# IntUltiMem_proto2.net
KiCad netlist of a schematic drawn in EAGLE
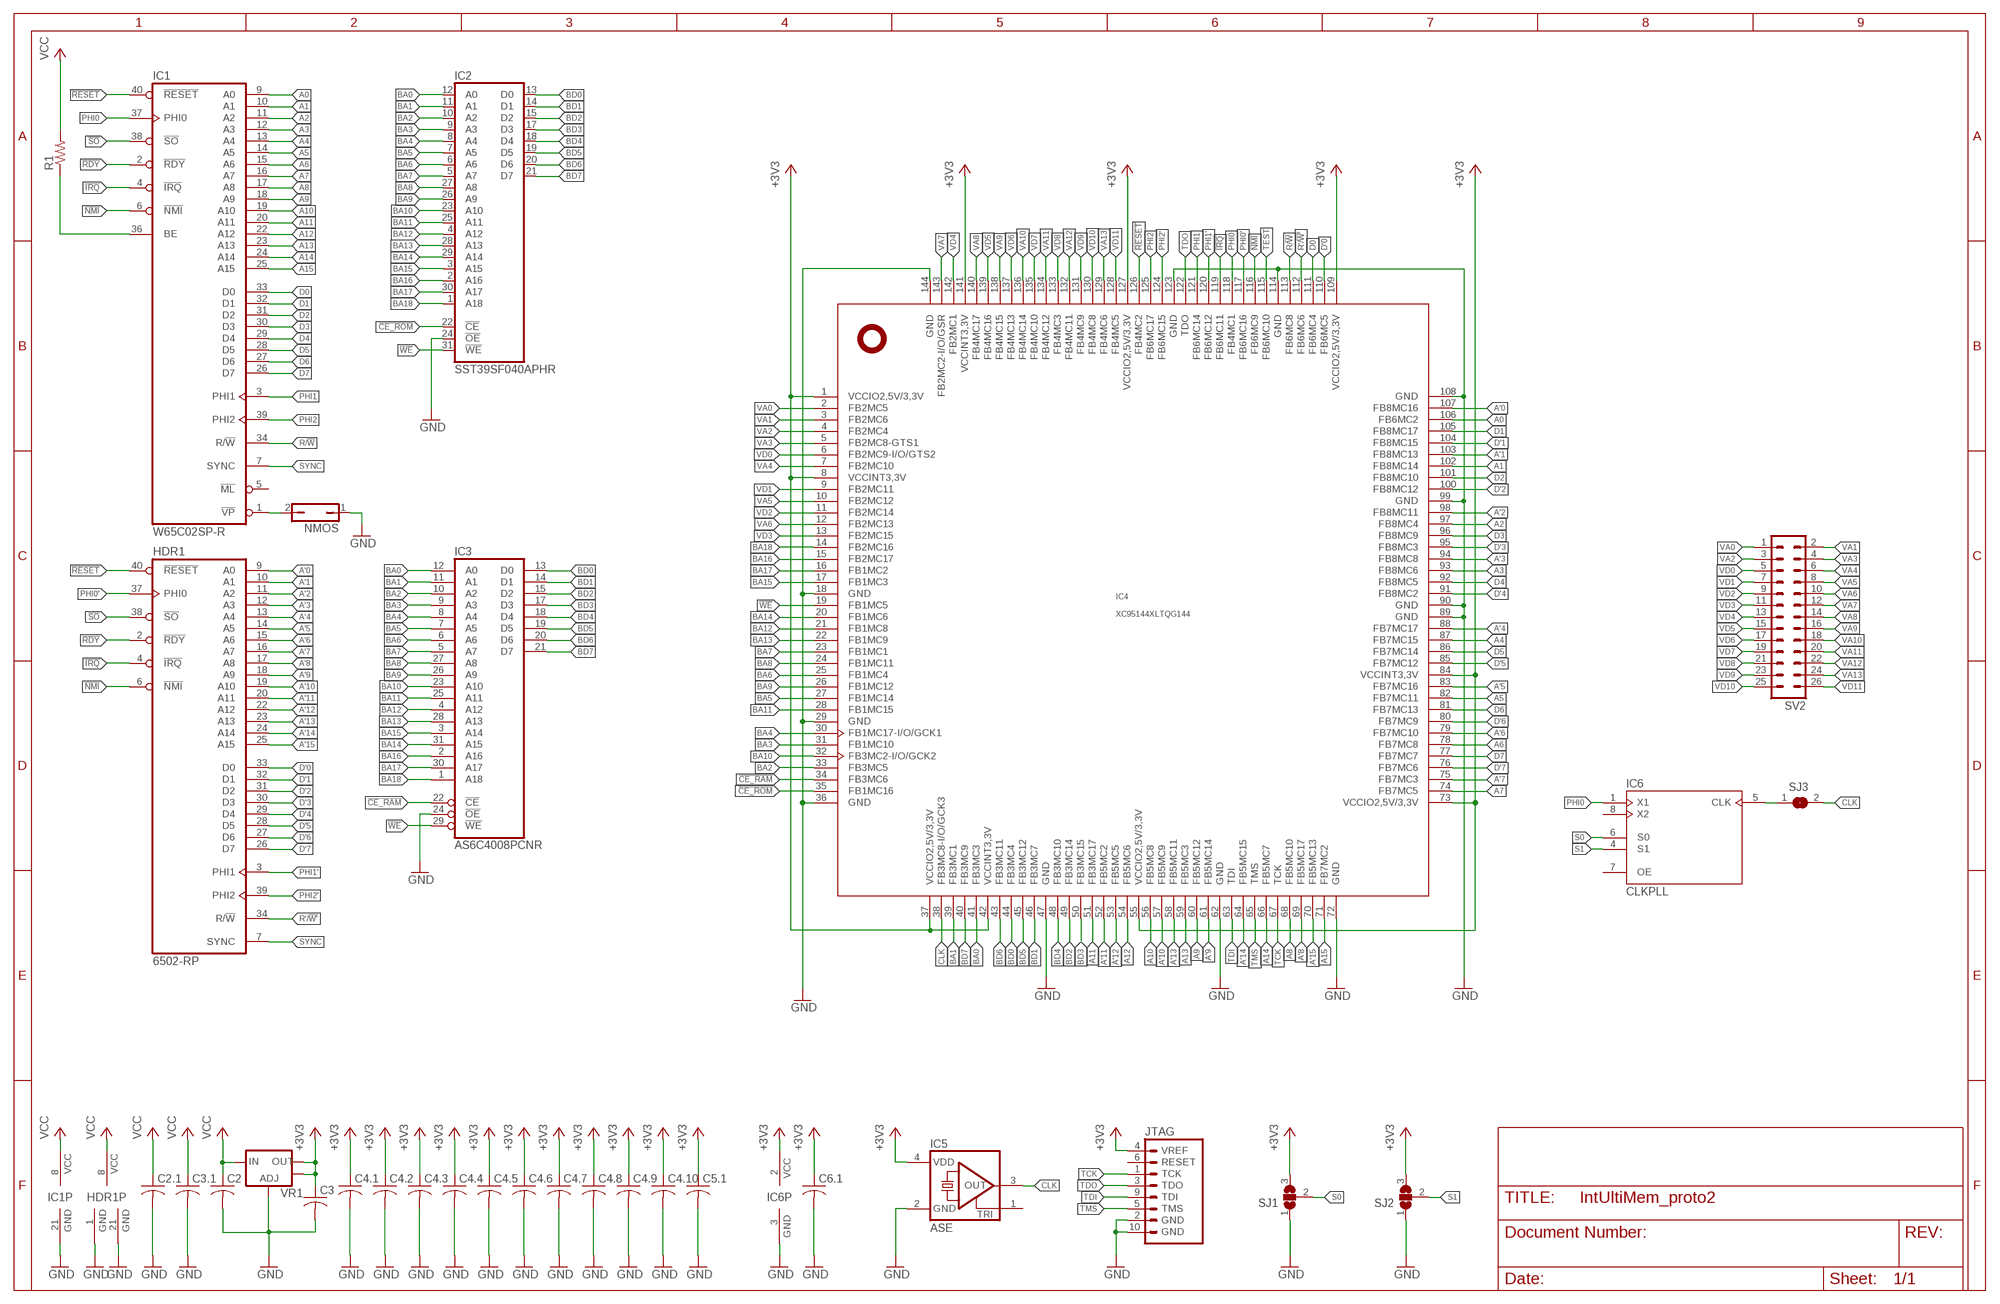
[diagram p0: schematic, sheet 1]

(export (version "E")
  (design (tool "Eeschema 10.0.6"))
  (components
    (comp (ref "C2")
      (value "C-USC0805")
      (footprint "eagle-import:C0805")
      (libsource (lib "eagle-import") (part "C-USC0805"))
    )
    (comp (ref "C2.1")
      (value "C-USC0402")
      (footprint "eagle-import:C0402")
      (libsource (lib "eagle-import") (part "C-USC0402"))
    )
    (comp (ref "C3")
      (value "C-USC0805")
      (footprint "eagle-import:C0805")
      (libsource (lib "eagle-import") (part "C-USC0805"))
    )
    (comp (ref "C3.1")
      (value "C-USC0402")
      (footprint "eagle-import:C0402")
      (libsource (lib "eagle-import") (part "C-USC0402"))
    )
    (comp (ref "C4.1")
      (value "C-USC0402")
      (footprint "eagle-import:C0402")
      (libsource (lib "eagle-import") (part "C-USC0402"))
    )
    (comp (ref "C4.2")
      (value "C-USC0402")
      (footprint "eagle-import:C0402")
      (libsource (lib "eagle-import") (part "C-USC0402"))
    )
    (comp (ref "C4.3")
      (value "C-USC0402")
      (footprint "eagle-import:C0402")
      (libsource (lib "eagle-import") (part "C-USC0402"))
    )
    (comp (ref "C4.4")
      (value "C-USC0402")
      (footprint "eagle-import:C0402")
      (libsource (lib "eagle-import") (part "C-USC0402"))
    )
    (comp (ref "C4.5")
      (value "C-USC0402")
      (footprint "eagle-import:C0402")
      (libsource (lib "eagle-import") (part "C-USC0402"))
    )
    (comp (ref "C4.6")
      (value "C-USC0402")
      (footprint "eagle-import:C0402")
      (libsource (lib "eagle-import") (part "C-USC0402"))
    )
    (comp (ref "C4.7")
      (value "C-USC0402")
      (footprint "eagle-import:C0402")
      (libsource (lib "eagle-import") (part "C-USC0402"))
    )
    (comp (ref "C4.8")
      (value "C-USC0402")
      (footprint "eagle-import:C0402")
      (libsource (lib "eagle-import") (part "C-USC0402"))
    )
    (comp (ref "C4.9")
      (value "C-USC0402")
      (footprint "eagle-import:C0402")
      (libsource (lib "eagle-import") (part "C-USC0402"))
    )
    (comp (ref "C4.10")
      (value "C-USC0402")
      (footprint "eagle-import:C0402")
      (libsource (lib "eagle-import") (part "C-USC0402"))
    )
    (comp (ref "C5.1")
      (value "C-USC0402")
      (footprint "eagle-import:C0402")
      (libsource (lib "eagle-import") (part "C-USC0402"))
    )
    (comp (ref "C6.1")
      (value "C-USC0402")
      (footprint "eagle-import:C0402")
      (libsource (lib "eagle-import") (part "C-USC0402"))
    )
    (comp (ref "HDR1")
      (value "6502-RP")
      (footprint "eagle-import:DIL40-ROUNDPAD")
      (libsource (lib "eagle-import") (part "6502-RP"))
    )
    (comp (ref "IC1")
      (value "W65C02SP-R")
      (footprint "eagle-import:DIL40-ROUNDPAD")
      (libsource (lib "eagle-import") (part "W65C02SP-R"))
    )
    (comp (ref "IC2")
      (value "SST39SF040APHR")
      (footprint "eagle-import:DIL32-RP")
      (libsource (lib "eagle-import") (part "SST39SF040APHR"))
    )
    (comp (ref "IC3")
      (value "AS6C4008PCNR")
      (footprint "eagle-import:DIL32-RP")
      (libsource (lib "eagle-import") (part "AS6C4008PCNR"))
    )
    (comp (ref "IC4")
      (value "XC95144XLTQG144")
      (footprint "eagle-import:TQFP144")
      (libsource (lib "eagle-import") (part "XC95144XLTQG144"))
    )
    (comp (ref "IC5")
      (value "ASE")
      (footprint "eagle-import:ASE")
      (libsource (lib "eagle-import") (part "ASE"))
    )
    (comp (ref "IC6")
      (value "CLKPLL")
      (footprint "eagle-import:SOIC8")
      (libsource (lib "eagle-import") (part "CLKPLL"))
    )
    (comp (ref "JTAG")
      (value "JTAG")
      (footprint "eagle-import:JTAG")
      (libsource (lib "eagle-import") (part "JTAG"))
    )
    (comp (ref "NMOS")
      (value "JP1Q")
      (footprint "eagle-import:JP1")
      (libsource (lib "eagle-import") (part "JP1Q"))
    )
    (comp (ref "R1")
      (value "R-US_R0402")
      (footprint "eagle-import:R0402")
      (libsource (lib "eagle-import") (part "R-US_R0402"))
    )
    (comp (ref "SJ1")
      (value "SJ2W")
      (footprint "eagle-import:SJ_2")
      (libsource (lib "eagle-import") (part "SJ2W"))
    )
    (comp (ref "SJ2")
      (value "SJ2W")
      (footprint "eagle-import:SJ_2")
      (libsource (lib "eagle-import") (part "SJ2W"))
    )
    (comp (ref "SJ3") (value "SJ") (footprint "eagle-import:SJ") (libsource (lib "eagle-import") (part "SJ")))
    (comp (ref "SV2")
      (value "MA13-2")
      (footprint "eagle-import:MA13-2")
      (libsource (lib "eagle-import") (part "MA13-2"))
    )
    (comp (ref "VR1")
      (value "V_REG_LM1117SOT223")
      (footprint "eagle-import:SOT223")
      (libsource (lib "eagle-import") (part "V_REG_LM1117SOT223"))
    )
  )
  (nets
    (net (code "1") (name "+3V3") (class "Default")
      (node (ref "C3") (pin "1") (pinfunction "1_1") (pintype "passive"))
      (node (ref "C4.1") (pin "1") (pinfunction "1_1") (pintype "passive"))
      (node (ref "C4.10") (pin "1") (pinfunction "1_1") (pintype "passive"))
      (node (ref "C4.2") (pin "1") (pinfunction "1_1") (pintype "passive"))
      (node (ref "C4.3") (pin "1") (pinfunction "1_1") (pintype "passive"))
      (node (ref "C4.4") (pin "1") (pinfunction "1_1") (pintype "passive"))
      (node (ref "C4.5") (pin "1") (pinfunction "1_1") (pintype "passive"))
      (node (ref "C4.6") (pin "1") (pinfunction "1_1") (pintype "passive"))
      (node (ref "C4.7") (pin "1") (pinfunction "1_1") (pintype "passive"))
      (node (ref "C4.8") (pin "1") (pinfunction "1_1") (pintype "passive"))
      (node (ref "C4.9") (pin "1") (pinfunction "1_1") (pintype "passive"))
      (node (ref "C5.1") (pin "1") (pinfunction "1_1") (pintype "passive"))
      (node (ref "C6.1") (pin "1") (pinfunction "1_1") (pintype "passive"))
      (node (ref "IC4") (pin "1") (pinfunction "VCCIO2,5V/3,3V_1") (pintype "power_in"))
      (node (ref "IC4") (pin "109") (pinfunction "VCCIO2,5V/3,3V_109") (pintype "power_in"))
      (node (ref "IC4") (pin "127") (pinfunction "VCCIO2,5V/3,3V_127") (pintype "power_in"))
      (node (ref "IC4") (pin "141") (pinfunction "VCCINT3,3V_141") (pintype "power_in"))
      (node (ref "IC4") (pin "37") (pinfunction "VCCIO2,5V/3,3V_37") (pintype "power_in"))
      (node (ref "IC4") (pin "42") (pinfunction "VCCINT3,3V_42") (pintype "power_in"))
      (node (ref "IC4") (pin "55") (pinfunction "VCCIO2,5V/3,3V_55") (pintype "power_in"))
      (node (ref "IC4") (pin "73") (pinfunction "VCCIO2,5V/3,3V_73") (pintype "power_in"))
      (node (ref "IC4") (pin "8") (pinfunction "VCCINT3,3V_8") (pintype "power_in"))
      (node (ref "IC4") (pin "84") (pinfunction "VCCINT3,3V_84") (pintype "power_in"))
      (node (ref "IC5") (pin "4") (pinfunction "VDD_4") (pintype "power_in"))
      (node (ref "IC6") (pin "2") (pinfunction "VCC_2") (pintype "power_in"))
      (node (ref "JTAG") (pin "4") (pinfunction "VREF_4") (pintype "power_in"))
      (node (ref "SJ1") (pin "3") (pinfunction "3_3") (pintype "passive"))
      (node (ref "SJ2") (pin "3") (pinfunction "3_3") (pintype "passive"))
      (node (ref "VR1") (pin "2") (pinfunction "OUT_2") (pintype "output"))
      (node (ref "VR1") (pin "4") (pinfunction "OUT_4") (pintype "output"))
    )
    (net (code "2") (name "/R'{slash}~{W'}") (class "Default")
      (node (ref "HDR1") (pin "34") (pinfunction "R/~{W}_34") (pintype "output"))
      (node (ref "IC4") (pin "112") (pinfunction "FB6MC6_112") (pintype "bidirectional"))
    )
    (net (code "3") (name "/R{slash}~{W}") (class "Default")
      (node (ref "IC1") (pin "34") (pinfunction "R/~{W}_34") (pintype "output"))
      (node (ref "IC4") (pin "113") (pinfunction "FB6MC8_113") (pintype "bidirectional"))
    )
    (net (code "4") (name "/~{CE_RAM}") (class "Default")
      (node (ref "IC3") (pin "22") (pinfunction "~{CE}_22") (pintype "input"))
      (node (ref "IC4") (pin "34") (pinfunction "FB3MC6_34") (pintype "bidirectional"))
    )
    (net (code "5") (name "/~{CE_ROM}") (class "Default")
      (node (ref "IC2") (pin "22") (pinfunction "~{CE}_22") (pintype "input"))
      (node (ref "IC4") (pin "35") (pinfunction "FB1MC16_35") (pintype "bidirectional"))
    )
    (net (code "6") (name "/~{IRQ}") (class "Default")
      (node (ref "HDR1") (pin "4") (pinfunction "~{IRQ}_4") (pintype "input"))
      (node (ref "IC1") (pin "4") (pinfunction "~{IRQ}_4") (pintype "input"))
      (node (ref "IC4") (pin "119") (pinfunction "FB6MC11_119") (pintype "bidirectional"))
    )
    (net (code "7") (name "/~{NMI}") (class "Default")
      (node (ref "HDR1") (pin "6") (pinfunction "~{NMI}_6") (pintype "input"))
      (node (ref "IC1") (pin "6") (pinfunction "~{NMI}_6") (pintype "input"))
      (node (ref "IC4") (pin "116") (pinfunction "FB6MC9_116") (pintype "bidirectional"))
    )
    (net (code "8") (name "/~{RDY}") (class "Default")
      (node (ref "HDR1") (pin "2") (pinfunction "~{RDY}_2") (pintype "input"))
      (node (ref "IC1") (pin "2") (pinfunction "~{RDY}_2") (pintype "bidirectional"))
    )
    (net (code "9") (name "/~{RESET}") (class "Default")
      (node (ref "HDR1") (pin "40") (pinfunction "~{RESET}_40") (pintype "input"))
      (node (ref "IC1") (pin "40") (pinfunction "~{RESET}_40") (pintype "input"))
      (node (ref "IC4") (pin "126") (pinfunction "FB4MC2_126") (pintype "bidirectional"))
    )
    (net (code "10") (name "/~{SO}") (class "Default")
      (node (ref "HDR1") (pin "38") (pinfunction "~{SO}_38") (pintype "input"))
      (node (ref "IC1") (pin "38") (pinfunction "~{SO}_38") (pintype "input"))
    )
    (net (code "11") (name "/~{WE}") (class "Default")
      (node (ref "IC2") (pin "31") (pinfunction "~{WE}_31") (pintype "input"))
      (node (ref "IC3") (pin "29") (pinfunction "~{WE}_29") (pintype "input"))
      (node (ref "IC4") (pin "19") (pinfunction "FB1MC5_19") (pintype "bidirectional"))
    )
    (net (code "12") (name "A'0") (class "Default")
      (node (ref "HDR1") (pin "9") (pinfunction "A0_9") (pintype "output"))
      (node (ref "IC4") (pin "107") (pinfunction "FB8MC16_107") (pintype "bidirectional"))
    )
    (net (code "13") (name "A'1") (class "Default")
      (node (ref "HDR1") (pin "10") (pinfunction "A1_10") (pintype "output"))
      (node (ref "IC4") (pin "103") (pinfunction "FB8MC13_103") (pintype "bidirectional"))
    )
    (net (code "14") (name "A'2") (class "Default")
      (node (ref "HDR1") (pin "11") (pinfunction "A2_11") (pintype "output"))
      (node (ref "IC4") (pin "98") (pinfunction "FB8MC11_98") (pintype "bidirectional"))
    )
    (net (code "15") (name "A'3") (class "Default")
      (node (ref "HDR1") (pin "12") (pinfunction "A3_12") (pintype "output"))
      (node (ref "IC4") (pin "94") (pinfunction "FB8MC8_94") (pintype "bidirectional"))
    )
    (net (code "16") (name "A'4") (class "Default")
      (node (ref "HDR1") (pin "13") (pinfunction "A4_13") (pintype "output"))
      (node (ref "IC4") (pin "88") (pinfunction "FB7MC17_88") (pintype "bidirectional"))
    )
    (net (code "17") (name "A'5") (class "Default")
      (node (ref "HDR1") (pin "14") (pinfunction "A5_14") (pintype "output"))
      (node (ref "IC4") (pin "83") (pinfunction "FB7MC16_83") (pintype "bidirectional"))
    )
    (net (code "18") (name "A'6") (class "Default")
      (node (ref "HDR1") (pin "15") (pinfunction "A6_15") (pintype "output"))
      (node (ref "IC4") (pin "79") (pinfunction "FB7MC10_79") (pintype "bidirectional"))
    )
    (net (code "19") (name "A'7") (class "Default")
      (node (ref "HDR1") (pin "16") (pinfunction "A7_16") (pintype "output"))
      (node (ref "IC4") (pin "75") (pinfunction "FB7MC3_75") (pintype "bidirectional"))
    )
    (net (code "20") (name "A'8") (class "Default")
      (node (ref "HDR1") (pin "17") (pinfunction "A8_17") (pintype "output"))
      (node (ref "IC4") (pin "69") (pinfunction "FB5MC17_69") (pintype "bidirectional"))
    )
    (net (code "21") (name "A'9") (class "Default")
      (node (ref "HDR1") (pin "18") (pinfunction "A9_18") (pintype "output"))
      (node (ref "IC4") (pin "61") (pinfunction "FB5MC14_61") (pintype "bidirectional"))
    )
    (net (code "22") (name "A'10") (class "Default")
      (node (ref "HDR1") (pin "19") (pinfunction "A10_19") (pintype "output"))
      (node (ref "IC4") (pin "57") (pinfunction "FB5MC9_57") (pintype "bidirectional"))
    )
    (net (code "23") (name "A'11") (class "Default")
      (node (ref "HDR1") (pin "20") (pinfunction "A11_20") (pintype "output"))
      (node (ref "IC4") (pin "52") (pinfunction "FB5MC2_52") (pintype "bidirectional"))
    )
    (net (code "24") (name "A'12") (class "Default")
      (node (ref "HDR1") (pin "22") (pinfunction "A12_22") (pintype "output"))
      (node (ref "IC4") (pin "53") (pinfunction "FB5MC5_53") (pintype "bidirectional"))
    )
    (net (code "25") (name "A'13") (class "Default")
      (node (ref "HDR1") (pin "23") (pinfunction "A13_23") (pintype "output"))
      (node (ref "IC4") (pin "58") (pinfunction "FB5MC11_58") (pintype "bidirectional"))
    )
    (net (code "26") (name "A'14") (class "Default")
      (node (ref "HDR1") (pin "24") (pinfunction "A14_24") (pintype "output"))
      (node (ref "IC4") (pin "64") (pinfunction "FB5MC15_64") (pintype "bidirectional"))
    )
    (net (code "27") (name "A'15") (class "Default")
      (node (ref "HDR1") (pin "25") (pinfunction "A15_25") (pintype "output"))
      (node (ref "IC4") (pin "70") (pinfunction "FB5MC13_70") (pintype "bidirectional"))
    )
    (net (code "28") (name "A0") (class "Default")
      (node (ref "IC1") (pin "9") (pinfunction "A0_9") (pintype "bidirectional"))
      (node (ref "IC4") (pin "106") (pinfunction "FB6MC2_106") (pintype "bidirectional"))
    )
    (net (code "29") (name "A1") (class "Default")
      (node (ref "IC1") (pin "10") (pinfunction "A1_10") (pintype "bidirectional"))
      (node (ref "IC4") (pin "102") (pinfunction "FB8MC14_102") (pintype "bidirectional"))
    )
    (net (code "30") (name "A2") (class "Default")
      (node (ref "IC1") (pin "11") (pinfunction "A2_11") (pintype "bidirectional"))
      (node (ref "IC4") (pin "97") (pinfunction "FB8MC4_97") (pintype "bidirectional"))
    )
    (net (code "31") (name "A3") (class "Default")
      (node (ref "IC1") (pin "12") (pinfunction "A3_12") (pintype "bidirectional"))
      (node (ref "IC4") (pin "93") (pinfunction "FB8MC6_93") (pintype "bidirectional"))
    )
    (net (code "32") (name "A4") (class "Default")
      (node (ref "IC1") (pin "13") (pinfunction "A4_13") (pintype "bidirectional"))
      (node (ref "IC4") (pin "87") (pinfunction "FB7MC15_87") (pintype "bidirectional"))
    )
    (net (code "33") (name "A5") (class "Default")
      (node (ref "IC1") (pin "14") (pinfunction "A5_14") (pintype "bidirectional"))
      (node (ref "IC4") (pin "82") (pinfunction "FB7MC11_82") (pintype "bidirectional"))
    )
    (net (code "34") (name "A6") (class "Default")
      (node (ref "IC1") (pin "15") (pinfunction "A6_15") (pintype "bidirectional"))
      (node (ref "IC4") (pin "78") (pinfunction "FB7MC8_78") (pintype "bidirectional"))
    )
    (net (code "35") (name "A7") (class "Default")
      (node (ref "IC1") (pin "16") (pinfunction "A7_16") (pintype "bidirectional"))
      (node (ref "IC4") (pin "74") (pinfunction "FB7MC5_74") (pintype "bidirectional"))
    )
    (net (code "36") (name "A8") (class "Default")
      (node (ref "IC1") (pin "17") (pinfunction "A8_17") (pintype "bidirectional"))
      (node (ref "IC4") (pin "68") (pinfunction "FB5MC10_68") (pintype "bidirectional"))
    )
    (net (code "37") (name "A9") (class "Default")
      (node (ref "IC1") (pin "18") (pinfunction "A9_18") (pintype "bidirectional"))
      (node (ref "IC4") (pin "60") (pinfunction "FB5MC12_60") (pintype "bidirectional"))
    )
    (net (code "38") (name "A10") (class "Default")
      (node (ref "IC1") (pin "19") (pinfunction "A10_19") (pintype "bidirectional"))
      (node (ref "IC4") (pin "56") (pinfunction "FB5MC8_56") (pintype "bidirectional"))
    )
    (net (code "39") (name "A11") (class "Default")
      (node (ref "IC1") (pin "20") (pinfunction "A11_20") (pintype "bidirectional"))
      (node (ref "IC4") (pin "51") (pinfunction "FB3MC17_51") (pintype "bidirectional"))
    )
    (net (code "40") (name "A12") (class "Default")
      (node (ref "IC1") (pin "22") (pinfunction "A12_22") (pintype "bidirectional"))
      (node (ref "IC4") (pin "54") (pinfunction "FB5MC6_54") (pintype "bidirectional"))
    )
    (net (code "41") (name "A13") (class "Default")
      (node (ref "IC1") (pin "23") (pinfunction "A13_23") (pintype "bidirectional"))
      (node (ref "IC4") (pin "59") (pinfunction "FB5MC3_59") (pintype "bidirectional"))
    )
    (net (code "42") (name "A14") (class "Default")
      (node (ref "IC1") (pin "24") (pinfunction "A14_24") (pintype "bidirectional"))
      (node (ref "IC4") (pin "66") (pinfunction "FB5MC7_66") (pintype "bidirectional"))
    )
    (net (code "43") (name "A15") (class "Default")
      (node (ref "IC1") (pin "25") (pinfunction "A15_25") (pintype "bidirectional"))
      (node (ref "IC4") (pin "71") (pinfunction "FB7MC2_71") (pintype "bidirectional"))
    )
    (net (code "44") (name "BA0") (class "Default")
      (node (ref "IC2") (pin "12") (pinfunction "A0_12") (pintype "input"))
      (node (ref "IC3") (pin "12") (pinfunction "A0_12") (pintype "input"))
      (node (ref "IC4") (pin "41") (pinfunction "FB3MC3_41") (pintype "bidirectional"))
    )
    (net (code "45") (name "BA1") (class "Default")
      (node (ref "IC2") (pin "11") (pinfunction "A1_11") (pintype "input"))
      (node (ref "IC3") (pin "11") (pinfunction "A1_11") (pintype "input"))
      (node (ref "IC4") (pin "39") (pinfunction "FB3MC1_39") (pintype "bidirectional"))
    )
    (net (code "46") (name "BA2") (class "Default")
      (node (ref "IC2") (pin "10") (pinfunction "A2_10") (pintype "input"))
      (node (ref "IC3") (pin "10") (pinfunction "A2_10") (pintype "input"))
      (node (ref "IC4") (pin "33") (pinfunction "FB3MC5_33") (pintype "bidirectional"))
    )
    (net (code "47") (name "BA3") (class "Default")
      (node (ref "IC2") (pin "9") (pinfunction "A3_9") (pintype "input"))
      (node (ref "IC3") (pin "9") (pinfunction "A3_9") (pintype "input"))
      (node (ref "IC4") (pin "31") (pinfunction "FB1MC10_31") (pintype "bidirectional"))
    )
    (net (code "48") (name "BA4") (class "Default")
      (node (ref "IC2") (pin "8") (pinfunction "A4_8") (pintype "input"))
      (node (ref "IC3") (pin "8") (pinfunction "A4_8") (pintype "input"))
      (node (ref "IC4") (pin "30") (pinfunction "FB1MC17-I/O/GCK1_30") (pintype "bidirectional"))
    )
    (net (code "49") (name "BA5") (class "Default")
      (node (ref "IC2") (pin "7") (pinfunction "A5_7") (pintype "input"))
      (node (ref "IC3") (pin "7") (pinfunction "A5_7") (pintype "input"))
      (node (ref "IC4") (pin "27") (pinfunction "FB1MC14_27") (pintype "bidirectional"))
    )
    (net (code "50") (name "BA6") (class "Default")
      (node (ref "IC2") (pin "6") (pinfunction "A6_6") (pintype "input"))
      (node (ref "IC3") (pin "6") (pinfunction "A6_6") (pintype "input"))
      (node (ref "IC4") (pin "25") (pinfunction "FB1MC4_25") (pintype "bidirectional"))
    )
    (net (code "51") (name "BA7") (class "Default")
      (node (ref "IC2") (pin "5") (pinfunction "A7_5") (pintype "input"))
      (node (ref "IC3") (pin "5") (pinfunction "A7_5") (pintype "input"))
      (node (ref "IC4") (pin "23") (pinfunction "FB1MC1_23") (pintype "bidirectional"))
    )
    (net (code "52") (name "BA8") (class "Default")
      (node (ref "IC2") (pin "27") (pinfunction "A8_27") (pintype "input"))
      (node (ref "IC3") (pin "27") (pinfunction "A8_27") (pintype "input"))
      (node (ref "IC4") (pin "24") (pinfunction "FB1MC11_24") (pintype "bidirectional"))
    )
    (net (code "53") (name "BA9") (class "Default")
      (node (ref "IC2") (pin "26") (pinfunction "A9_26") (pintype "input"))
      (node (ref "IC3") (pin "26") (pinfunction "A9_26") (pintype "input"))
      (node (ref "IC4") (pin "26") (pinfunction "FB1MC12_26") (pintype "bidirectional"))
    )
    (net (code "54") (name "BA10") (class "Default")
      (node (ref "IC2") (pin "23") (pinfunction "A10_23") (pintype "input"))
      (node (ref "IC3") (pin "23") (pinfunction "A10_23") (pintype "input"))
      (node (ref "IC4") (pin "32") (pinfunction "FB3MC2-I/O/GCK2_32") (pintype "bidirectional"))
    )
    (net (code "55") (name "BA11") (class "Default")
      (node (ref "IC2") (pin "25") (pinfunction "A11_25") (pintype "input"))
      (node (ref "IC3") (pin "25") (pinfunction "A11_25") (pintype "input"))
      (node (ref "IC4") (pin "28") (pinfunction "FB1MC15_28") (pintype "bidirectional"))
    )
    (net (code "56") (name "BA12") (class "Default")
      (node (ref "IC2") (pin "4") (pinfunction "A12_4") (pintype "input"))
      (node (ref "IC3") (pin "4") (pinfunction "A12_4") (pintype "input"))
      (node (ref "IC4") (pin "21") (pinfunction "FB1MC8_21") (pintype "bidirectional"))
    )
    (net (code "57") (name "BA13") (class "Default")
      (node (ref "IC2") (pin "28") (pinfunction "A13_28") (pintype "input"))
      (node (ref "IC3") (pin "28") (pinfunction "A13_28") (pintype "input"))
      (node (ref "IC4") (pin "22") (pinfunction "FB1MC9_22") (pintype "bidirectional"))
    )
    (net (code "58") (name "BA14") (class "Default")
      (node (ref "IC2") (pin "29") (pinfunction "A14_29") (pintype "input"))
      (node (ref "IC3") (pin "31") (pinfunction "A15_31") (pintype "input"))
      (node (ref "IC4") (pin "20") (pinfunction "FB1MC6_20") (pintype "bidirectional"))
    )
    (net (code "59") (name "BA15") (class "Default")
      (node (ref "IC2") (pin "3") (pinfunction "A15_3") (pintype "input"))
      (node (ref "IC3") (pin "3") (pinfunction "A14_3") (pintype "input"))
      (node (ref "IC4") (pin "17") (pinfunction "FB1MC3_17") (pintype "bidirectional"))
    )
    (net (code "60") (name "BA16") (class "Default")
      (node (ref "IC2") (pin "2") (pinfunction "A16_2") (pintype "input"))
      (node (ref "IC3") (pin "2") (pinfunction "A16_2") (pintype "input"))
      (node (ref "IC4") (pin "15") (pinfunction "FB2MC17_15") (pintype "bidirectional"))
    )
    (net (code "61") (name "BA17") (class "Default")
      (node (ref "IC2") (pin "30") (pinfunction "A17_30") (pintype "input"))
      (node (ref "IC3") (pin "30") (pinfunction "A17_30") (pintype "input"))
      (node (ref "IC4") (pin "16") (pinfunction "FB1MC2_16") (pintype "bidirectional"))
    )
    (net (code "62") (name "BA18") (class "Default")
      (node (ref "IC2") (pin "1") (pinfunction "A18_1") (pintype "input"))
      (node (ref "IC3") (pin "1") (pinfunction "A18_1") (pintype "input"))
      (node (ref "IC4") (pin "14") (pinfunction "FB2MC16_14") (pintype "bidirectional"))
    )
    (net (code "63") (name "BD0") (class "Default")
      (node (ref "IC2") (pin "13") (pinfunction "D0_13") (pintype "bidirectional"))
      (node (ref "IC3") (pin "13") (pinfunction "D0_13") (pintype "bidirectional"))
      (node (ref "IC4") (pin "44") (pinfunction "FB3MC4_44") (pintype "bidirectional"))
    )
    (net (code "64") (name "BD1") (class "Default")
      (node (ref "IC2") (pin "14") (pinfunction "D1_14") (pintype "bidirectional"))
      (node (ref "IC3") (pin "14") (pinfunction "D1_14") (pintype "bidirectional"))
      (node (ref "IC4") (pin "46") (pinfunction "FB3MC7_46") (pintype "bidirectional"))
    )
    (net (code "65") (name "BD2") (class "Default")
      (node (ref "IC2") (pin "15") (pinfunction "D2_15") (pintype "bidirectional"))
      (node (ref "IC3") (pin "15") (pinfunction "D2_15") (pintype "bidirectional"))
      (node (ref "IC4") (pin "49") (pinfunction "FB3MC14_49") (pintype "bidirectional"))
    )
    (net (code "66") (name "BD3") (class "Default")
      (node (ref "IC2") (pin "17") (pinfunction "D3_17") (pintype "bidirectional"))
      (node (ref "IC3") (pin "17") (pinfunction "D3_17") (pintype "bidirectional"))
      (node (ref "IC4") (pin "50") (pinfunction "FB3MC15_50") (pintype "bidirectional"))
    )
    (net (code "67") (name "BD4") (class "Default")
      (node (ref "IC2") (pin "18") (pinfunction "D4_18") (pintype "bidirectional"))
      (node (ref "IC3") (pin "18") (pinfunction "D4_18") (pintype "bidirectional"))
      (node (ref "IC4") (pin "48") (pinfunction "FB3MC10_48") (pintype "bidirectional"))
    )
    (net (code "68") (name "BD5") (class "Default")
      (node (ref "IC2") (pin "19") (pinfunction "D5_19") (pintype "bidirectional"))
      (node (ref "IC3") (pin "19") (pinfunction "D5_19") (pintype "bidirectional"))
      (node (ref "IC4") (pin "45") (pinfunction "FB3MC12_45") (pintype "bidirectional"))
    )
    (net (code "69") (name "BD6") (class "Default")
      (node (ref "IC2") (pin "20") (pinfunction "D6_20") (pintype "bidirectional"))
      (node (ref "IC3") (pin "20") (pinfunction "D6_20") (pintype "bidirectional"))
      (node (ref "IC4") (pin "43") (pinfunction "FB3MC11_43") (pintype "bidirectional"))
    )
    (net (code "70") (name "BD7") (class "Default")
      (node (ref "IC2") (pin "21") (pinfunction "D7_21") (pintype "bidirectional"))
      (node (ref "IC3") (pin "21") (pinfunction "D7_21") (pintype "bidirectional"))
      (node (ref "IC4") (pin "40") (pinfunction "FB3MC9_40") (pintype "bidirectional"))
    )
    (net (code "71") (name "CLK") (class "Default")
      (node (ref "IC4") (pin "38") (pinfunction "FB3MC8-I/O/GCK3_38") (pintype "bidirectional"))
      (node (ref "IC5") (pin "3") (pinfunction "OUT_3") (pintype "output"))
      (node (ref "SJ3") (pin "2") (pinfunction "2_2") (pintype "passive"))
    )
    (net (code "72") (name "D'0") (class "Default")
      (node (ref "HDR1") (pin "33") (pinfunction "D0_33") (pintype "bidirectional"))
      (node (ref "IC4") (pin "110") (pinfunction "FB6MC5_110") (pintype "bidirectional"))
    )
    (net (code "73") (name "D'1") (class "Default")
      (node (ref "HDR1") (pin "32") (pinfunction "D1_32") (pintype "bidirectional"))
      (node (ref "IC4") (pin "104") (pinfunction "FB8MC15_104") (pintype "bidirectional"))
    )
    (net (code "74") (name "D'2") (class "Default")
      (node (ref "HDR1") (pin "31") (pinfunction "D2_31") (pintype "bidirectional"))
      (node (ref "IC4") (pin "100") (pinfunction "FB8MC12_100") (pintype "bidirectional"))
    )
    (net (code "75") (name "D'3") (class "Default")
      (node (ref "HDR1") (pin "30") (pinfunction "D3_30") (pintype "bidirectional"))
      (node (ref "IC4") (pin "95") (pinfunction "FB8MC3_95") (pintype "bidirectional"))
    )
    (net (code "76") (name "D'4") (class "Default")
      (node (ref "HDR1") (pin "29") (pinfunction "D4_29") (pintype "bidirectional"))
      (node (ref "IC4") (pin "91") (pinfunction "FB8MC2_91") (pintype "bidirectional"))
    )
    (net (code "77") (name "D'5") (class "Default")
      (node (ref "HDR1") (pin "28") (pinfunction "D5_28") (pintype "bidirectional"))
      (node (ref "IC4") (pin "85") (pinfunction "FB7MC12_85") (pintype "bidirectional"))
    )
    (net (code "78") (name "D'6") (class "Default")
      (node (ref "HDR1") (pin "27") (pinfunction "D6_27") (pintype "bidirectional"))
      (node (ref "IC4") (pin "80") (pinfunction "FB7MC9_80") (pintype "bidirectional"))
    )
    (net (code "79") (name "D'7") (class "Default")
      (node (ref "HDR1") (pin "26") (pinfunction "D7_26") (pintype "bidirectional"))
      (node (ref "IC4") (pin "76") (pinfunction "FB7MC6_76") (pintype "bidirectional"))
    )
    (net (code "80") (name "D0") (class "Default")
      (node (ref "IC1") (pin "33") (pinfunction "D0_33") (pintype "bidirectional"))
      (node (ref "IC4") (pin "111") (pinfunction "FB6MC4_111") (pintype "bidirectional"))
    )
    (net (code "81") (name "D1") (class "Default")
      (node (ref "IC1") (pin "32") (pinfunction "D1_32") (pintype "bidirectional"))
      (node (ref "IC4") (pin "105") (pinfunction "FB8MC17_105") (pintype "bidirectional"))
    )
    (net (code "82") (name "D2") (class "Default")
      (node (ref "IC1") (pin "31") (pinfunction "D2_31") (pintype "bidirectional"))
      (node (ref "IC4") (pin "101") (pinfunction "FB8MC10_101") (pintype "bidirectional"))
    )
    (net (code "83") (name "D3") (class "Default")
      (node (ref "IC1") (pin "30") (pinfunction "D3_30") (pintype "bidirectional"))
      (node (ref "IC4") (pin "96") (pinfunction "FB8MC9_96") (pintype "bidirectional"))
    )
    (net (code "84") (name "D4") (class "Default")
      (node (ref "IC1") (pin "29") (pinfunction "D4_29") (pintype "bidirectional"))
      (node (ref "IC4") (pin "92") (pinfunction "FB8MC5_92") (pintype "bidirectional"))
    )
    (net (code "85") (name "D5") (class "Default")
      (node (ref "IC1") (pin "28") (pinfunction "D5_28") (pintype "bidirectional"))
      (node (ref "IC4") (pin "86") (pinfunction "FB7MC14_86") (pintype "bidirectional"))
    )
    (net (code "86") (name "D6") (class "Default")
      (node (ref "IC1") (pin "27") (pinfunction "D6_27") (pintype "bidirectional"))
      (node (ref "IC4") (pin "81") (pinfunction "FB7MC13_81") (pintype "bidirectional"))
    )
    (net (code "87") (name "D7") (class "Default")
      (node (ref "IC1") (pin "26") (pinfunction "D7_26") (pintype "bidirectional"))
      (node (ref "IC4") (pin "77") (pinfunction "FB7MC7_77") (pintype "bidirectional"))
    )
    (net (code "88") (name "GND") (class "Default")
      (node (ref "C2") (pin "2") (pinfunction "2_2") (pintype "passive"))
      (node (ref "C2.1") (pin "2") (pinfunction "2_2") (pintype "passive"))
      (node (ref "C3") (pin "2") (pinfunction "2_2") (pintype "passive"))
      (node (ref "C3.1") (pin "2") (pinfunction "2_2") (pintype "passive"))
      (node (ref "C4.1") (pin "2") (pinfunction "2_2") (pintype "passive"))
      (node (ref "C4.10") (pin "2") (pinfunction "2_2") (pintype "passive"))
      (node (ref "C4.2") (pin "2") (pinfunction "2_2") (pintype "passive"))
      (node (ref "C4.3") (pin "2") (pinfunction "2_2") (pintype "passive"))
      (node (ref "C4.4") (pin "2") (pinfunction "2_2") (pintype "passive"))
      (node (ref "C4.5") (pin "2") (pinfunction "2_2") (pintype "passive"))
      (node (ref "C4.6") (pin "2") (pinfunction "2_2") (pintype "passive"))
      (node (ref "C4.7") (pin "2") (pinfunction "2_2") (pintype "passive"))
      (node (ref "C4.8") (pin "2") (pinfunction "2_2") (pintype "passive"))
      (node (ref "C4.9") (pin "2") (pinfunction "2_2") (pintype "passive"))
      (node (ref "C5.1") (pin "2") (pinfunction "2_2") (pintype "passive"))
      (node (ref "C6.1") (pin "2") (pinfunction "2_2") (pintype "passive"))
      (node (ref "HDR1") (pin "1") (pinfunction "GND_1") (pintype "power_in"))
      (node (ref "HDR1") (pin "21") (pinfunction "GND_21") (pintype "power_in"))
      (node (ref "IC1") (pin "21") (pinfunction "GND_21") (pintype "power_in"))
      (node (ref "IC2") (pin "24") (pinfunction "~{OE}_24") (pintype "input"))
      (node (ref "IC3") (pin "24") (pinfunction "~{OE}_24") (pintype "input"))
      (node (ref "IC4") (pin "108") (pinfunction "GND_108") (pintype "power_in"))
      (node (ref "IC4") (pin "114") (pinfunction "GND_114") (pintype "power_in"))
      (node (ref "IC4") (pin "123") (pinfunction "GND_123") (pintype "power_in"))
      (node (ref "IC4") (pin "144") (pinfunction "GND_144") (pintype "power_in"))
      (node (ref "IC4") (pin "18") (pinfunction "GND_18") (pintype "power_in"))
      (node (ref "IC4") (pin "29") (pinfunction "GND_29") (pintype "power_in"))
      (node (ref "IC4") (pin "36") (pinfunction "GND_36") (pintype "power_in"))
      (node (ref "IC4") (pin "47") (pinfunction "GND_47") (pintype "power_in"))
      (node (ref "IC4") (pin "62") (pinfunction "GND_62") (pintype "power_in"))
      (node (ref "IC4") (pin "72") (pinfunction "GND_72") (pintype "power_in"))
      (node (ref "IC4") (pin "89") (pinfunction "GND_89") (pintype "bidirectional"))
      (node (ref "IC4") (pin "90") (pinfunction "GND_90") (pintype "bidirectional"))
      (node (ref "IC4") (pin "99") (pinfunction "GND_99") (pintype "power_in"))
      (node (ref "IC5") (pin "2") (pinfunction "GND_2") (pintype "power_in"))
      (node (ref "IC6") (pin "3") (pinfunction "GND_3") (pintype "power_in"))
      (node (ref "JTAG") (pin "10") (pinfunction "GND_10") (pintype "power_in"))
      (node (ref "JTAG") (pin "2") (pinfunction "GND_2") (pintype "power_in"))
      (node (ref "NMOS") (pin "1") (pinfunction "1_1") (pintype "passive"))
      (node (ref "SJ1") (pin "1") (pinfunction "1_1") (pintype "passive"))
      (node (ref "SJ2") (pin "1") (pinfunction "1_1") (pintype "passive"))
      (node (ref "VR1") (pin "1") (pinfunction "ADJ_1") (pintype "input"))
    )
    (net (code "89") (name "Net-(IC1A-BE)") (class "Default")
      (node (ref "IC1") (pin "36") (pinfunction "BE_36") (pintype "input"))
      (node (ref "R1") (pin "1") (pinfunction "1_1") (pintype "passive"))
    )
    (net (code "90") (name "Net-(IC1A-~{VP})") (class "Default")
      (node (ref "IC1") (pin "1") (pinfunction "~{VP}_1") (pintype "output"))
      (node (ref "NMOS") (pin "2") (pinfunction "2_2") (pintype "passive"))
    )
    (net (code "91") (name "Net-(IC6A-CLK)") (class "Default")
      (node (ref "IC6") (pin "5") (pinfunction "CLK_5") (pintype "bidirectional"))
      (node (ref "SJ3") (pin "1") (pinfunction "1_1") (pintype "passive"))
    )
    (net (code "92") (name "PHI0") (class "Default")
      (node (ref "IC1") (pin "37") (pinfunction "PHI0_37") (pintype "input"))
      (node (ref "IC4") (pin "118") (pinfunction "FB4MC1_118") (pintype "bidirectional"))
      (node (ref "IC6") (pin "1") (pinfunction "X1_1") (pintype "bidirectional"))
    )
    (net (code "93") (name "PHI0'") (class "Default")
      (node (ref "HDR1") (pin "37") (pinfunction "PHI0_37") (pintype "input"))
      (node (ref "IC4") (pin "117") (pinfunction "FB6MC16_117") (pintype "bidirectional"))
    )
    (net (code "94") (name "PHI1") (class "Default")
      (node (ref "IC1") (pin "3") (pinfunction "PHI1_3") (pintype "output"))
      (node (ref "IC4") (pin "121") (pinfunction "FB6MC14_121") (pintype "bidirectional"))
    )
    (net (code "95") (name "PHI1'") (class "Default")
      (node (ref "HDR1") (pin "3") (pinfunction "PHI1_3") (pintype "output"))
      (node (ref "IC4") (pin "120") (pinfunction "FB6MC12_120") (pintype "bidirectional"))
    )
    (net (code "96") (name "PHI2") (class "Default")
      (node (ref "IC1") (pin "39") (pinfunction "PHI2_39") (pintype "output"))
      (node (ref "IC4") (pin "125") (pinfunction "FB6MC17_125") (pintype "bidirectional"))
    )
    (net (code "97") (name "PHI2'") (class "Default")
      (node (ref "HDR1") (pin "39") (pinfunction "PHI2_39") (pintype "output"))
      (node (ref "IC4") (pin "124") (pinfunction "FB6MC15_124") (pintype "bidirectional"))
    )
    (net (code "98") (name "S0") (class "Default")
      (node (ref "IC6") (pin "6") (pinfunction "S0_6") (pintype "bidirectional"))
      (node (ref "SJ1") (pin "2") (pinfunction "2_2") (pintype "passive"))
    )
    (net (code "99") (name "S1") (class "Default")
      (node (ref "IC6") (pin "4") (pinfunction "S1_4") (pintype "bidirectional"))
      (node (ref "SJ2") (pin "2") (pinfunction "2_2") (pintype "passive"))
    )
    (net (code "100") (name "SYNC") (class "Default")
      (node (ref "HDR1") (pin "7") (pinfunction "SYNC_7") (pintype "output"))
      (node (ref "IC1") (pin "7") (pinfunction "SYNC_7") (pintype "output"))
    )
    (net (code "101") (name "TCK") (class "Default")
      (node (ref "IC4") (pin "67") (pinfunction "TCK_67") (pintype "bidirectional"))
      (node (ref "JTAG") (pin "1") (pinfunction "TCK_1") (pintype "output"))
    )
    (net (code "102") (name "TDI") (class "Default")
      (node (ref "IC4") (pin "63") (pinfunction "TDI_63") (pintype "bidirectional"))
      (node (ref "JTAG") (pin "9") (pinfunction "TDI_9") (pintype "input"))
    )
    (net (code "103") (name "TDO") (class "Default")
      (node (ref "IC4") (pin "122") (pinfunction "TDO_122") (pintype "bidirectional"))
      (node (ref "JTAG") (pin "3") (pinfunction "TDO_3") (pintype "output"))
    )
    (net (code "104") (name "TEST") (class "Default")
      (node (ref "IC4") (pin "115") (pinfunction "FB6MC10_115") (pintype "bidirectional"))
    )
    (net (code "105") (name "TMS") (class "Default")
      (node (ref "IC4") (pin "65") (pinfunction "TMS_65") (pintype "bidirectional"))
      (node (ref "JTAG") (pin "5") (pinfunction "TMS_5") (pintype "output"))
    )
    (net (code "106") (name "VA0") (class "Default")
      (node (ref "IC4") (pin "2") (pinfunction "FB2MC5_2") (pintype "bidirectional"))
      (node (ref "SV2") (pin "1") (pinfunction "1_1") (pintype "passive"))
    )
    (net (code "107") (name "VA1") (class "Default")
      (node (ref "IC4") (pin "3") (pinfunction "FB2MC6_3") (pintype "bidirectional"))
      (node (ref "SV2") (pin "2") (pinfunction "2_2") (pintype "passive"))
    )
    (net (code "108") (name "VA2") (class "Default")
      (node (ref "IC4") (pin "4") (pinfunction "FB2MC4_4") (pintype "bidirectional"))
      (node (ref "SV2") (pin "3") (pinfunction "3_3") (pintype "passive"))
    )
    (net (code "109") (name "VA3") (class "Default")
      (node (ref "IC4") (pin "5") (pinfunction "FB2MC8-GTS1_5") (pintype "bidirectional"))
      (node (ref "SV2") (pin "4") (pinfunction "4_4") (pintype "passive"))
    )
    (net (code "110") (name "VA4") (class "Default")
      (node (ref "IC4") (pin "7") (pinfunction "FB2MC10_7") (pintype "bidirectional"))
      (node (ref "SV2") (pin "6") (pinfunction "6_6") (pintype "passive"))
    )
    (net (code "111") (name "VA5") (class "Default")
      (node (ref "IC4") (pin "10") (pinfunction "FB2MC12_10") (pintype "bidirectional"))
      (node (ref "SV2") (pin "8") (pinfunction "8_8") (pintype "passive"))
    )
    (net (code "112") (name "VA6") (class "Default")
      (node (ref "IC4") (pin "12") (pinfunction "FB2MC13_12") (pintype "bidirectional"))
      (node (ref "SV2") (pin "10") (pinfunction "10_10") (pintype "passive"))
    )
    (net (code "113") (name "VA7") (class "Default")
      (node (ref "IC4") (pin "143") (pinfunction "FB2MC2-I/O/GSR_143") (pintype "power_in"))
      (node (ref "SV2") (pin "12") (pinfunction "12_12") (pintype "passive"))
    )
    (net (code "114") (name "VA8") (class "Default")
      (node (ref "IC4") (pin "140") (pinfunction "FB4MC17_140") (pintype "bidirectional"))
      (node (ref "SV2") (pin "14") (pinfunction "14_14") (pintype "passive"))
    )
    (net (code "115") (name "VA9") (class "Default")
      (node (ref "IC4") (pin "138") (pinfunction "FB4MC15_138") (pintype "bidirectional"))
      (node (ref "SV2") (pin "16") (pinfunction "16_16") (pintype "passive"))
    )
    (net (code "116") (name "VA10") (class "Default")
      (node (ref "IC4") (pin "136") (pinfunction "FB4MC14_136") (pintype "bidirectional"))
      (node (ref "SV2") (pin "18") (pinfunction "18_18") (pintype "passive"))
    )
    (net (code "117") (name "VA11") (class "Default")
      (node (ref "IC4") (pin "134") (pinfunction "FB4MC12_134") (pintype "bidirectional"))
      (node (ref "SV2") (pin "20") (pinfunction "20_20") (pintype "passive"))
    )
    (net (code "118") (name "VA12") (class "Default")
      (node (ref "IC4") (pin "132") (pinfunction "FB4MC11_132") (pintype "bidirectional"))
      (node (ref "SV2") (pin "22") (pinfunction "22_22") (pintype "passive"))
    )
    (net (code "119") (name "VA13") (class "Default")
      (node (ref "IC4") (pin "129") (pinfunction "FB4MC6_129") (pintype "bidirectional"))
      (node (ref "SV2") (pin "24") (pinfunction "24_24") (pintype "passive"))
    )
    (net (code "120") (name "VCC") (class "Default")
      (node (ref "C2") (pin "1") (pinfunction "1_1") (pintype "passive"))
      (node (ref "C2.1") (pin "1") (pinfunction "1_1") (pintype "passive"))
      (node (ref "C3.1") (pin "1") (pinfunction "1_1") (pintype "passive"))
      (node (ref "HDR1") (pin "8") (pinfunction "VCC_8") (pintype "power_in"))
      (node (ref "IC1") (pin "8") (pinfunction "VCC_8") (pintype "power_in"))
      (node (ref "R1") (pin "2") (pinfunction "2_2") (pintype "passive"))
      (node (ref "VR1") (pin "3") (pinfunction "IN_3") (pintype "input"))
    )
    (net (code "121") (name "VD0") (class "Default")
      (node (ref "IC4") (pin "6") (pinfunction "FB2MC9-I/O/GTS2_6") (pintype "bidirectional"))
      (node (ref "SV2") (pin "5") (pinfunction "5_5") (pintype "passive"))
    )
    (net (code "122") (name "VD1") (class "Default")
      (node (ref "IC4") (pin "9") (pinfunction "FB2MC11_9") (pintype "bidirectional"))
      (node (ref "SV2") (pin "7") (pinfunction "7_7") (pintype "passive"))
    )
    (net (code "123") (name "VD2") (class "Default")
      (node (ref "IC4") (pin "11") (pinfunction "FB2MC14_11") (pintype "bidirectional"))
      (node (ref "SV2") (pin "9") (pinfunction "9_9") (pintype "passive"))
    )
    (net (code "124") (name "VD3") (class "Default")
      (node (ref "IC4") (pin "13") (pinfunction "FB2MC15_13") (pintype "bidirectional"))
      (node (ref "SV2") (pin "11") (pinfunction "11_11") (pintype "passive"))
    )
    (net (code "125") (name "VD4") (class "Default")
      (node (ref "IC4") (pin "142") (pinfunction "FB2MC1_142") (pintype "bidirectional"))
      (node (ref "SV2") (pin "13") (pinfunction "13_13") (pintype "passive"))
    )
    (net (code "126") (name "VD5") (class "Default")
      (node (ref "IC4") (pin "139") (pinfunction "FB4MC16_139") (pintype "bidirectional"))
      (node (ref "SV2") (pin "15") (pinfunction "15_15") (pintype "passive"))
    )
    (net (code "127") (name "VD6") (class "Default")
      (node (ref "IC4") (pin "137") (pinfunction "FB4MC13_137") (pintype "bidirectional"))
      (node (ref "SV2") (pin "17") (pinfunction "17_17") (pintype "passive"))
    )
    (net (code "128") (name "VD7") (class "Default")
      (node (ref "IC4") (pin "135") (pinfunction "FB4MC10_135") (pintype "bidirectional"))
      (node (ref "SV2") (pin "19") (pinfunction "19_19") (pintype "passive"))
    )
    (net (code "129") (name "VD8") (class "Default")
      (node (ref "IC4") (pin "133") (pinfunction "FB4MC3_133") (pintype "bidirectional"))
      (node (ref "SV2") (pin "21") (pinfunction "21_21") (pintype "passive"))
    )
    (net (code "130") (name "VD9") (class "Default")
      (node (ref "IC4") (pin "131") (pinfunction "FB4MC9_131") (pintype "bidirectional"))
      (node (ref "SV2") (pin "23") (pinfunction "23_23") (pintype "passive"))
    )
    (net (code "131") (name "VD10") (class "Default")
      (node (ref "IC4") (pin "130") (pinfunction "FB4MC8_130") (pintype "bidirectional"))
      (node (ref "SV2") (pin "25") (pinfunction "25_25") (pintype "passive"))
    )
    (net (code "132") (name "VD11") (class "Default")
      (node (ref "IC4") (pin "128") (pinfunction "FB4MC5_128") (pintype "bidirectional"))
      (node (ref "SV2") (pin "26") (pinfunction "26_26") (pintype "passive"))
    )
    (net (code "133") (name "unconnected-(IC1A-~{ML}-Pad5)") (class "Default")
      (node (ref "IC1") (pin "5") (pinfunction "~{ML}_5") (pintype "output"))
    )
    (net (code "134") (name "unconnected-(IC5-TRI-Pad1)") (class "Default")
      (node (ref "IC5") (pin "1") (pinfunction "TRI_1") (pintype "input"))
    )
    (net (code "135") (name "unconnected-(IC6A-OE-Pad7)") (class "Default")
      (node (ref "IC6") (pin "7") (pinfunction "OE_7") (pintype "input"))
    )
    (net (code "136") (name "unconnected-(IC6A-X2-Pad8)") (class "Default")
      (node (ref "IC6") (pin "8") (pinfunction "X2_8") (pintype "bidirectional"))
    )
    (net (code "137") (name "unconnected-(JTAG-RESET-Pad6)") (class "Default")
      (node (ref "JTAG") (pin "6") (pinfunction "RESET_6") (pintype "output"))
    )
  )
)
